# OBDII-Ist.net
KiCad netlist of a schematic drawn in Altium Designer
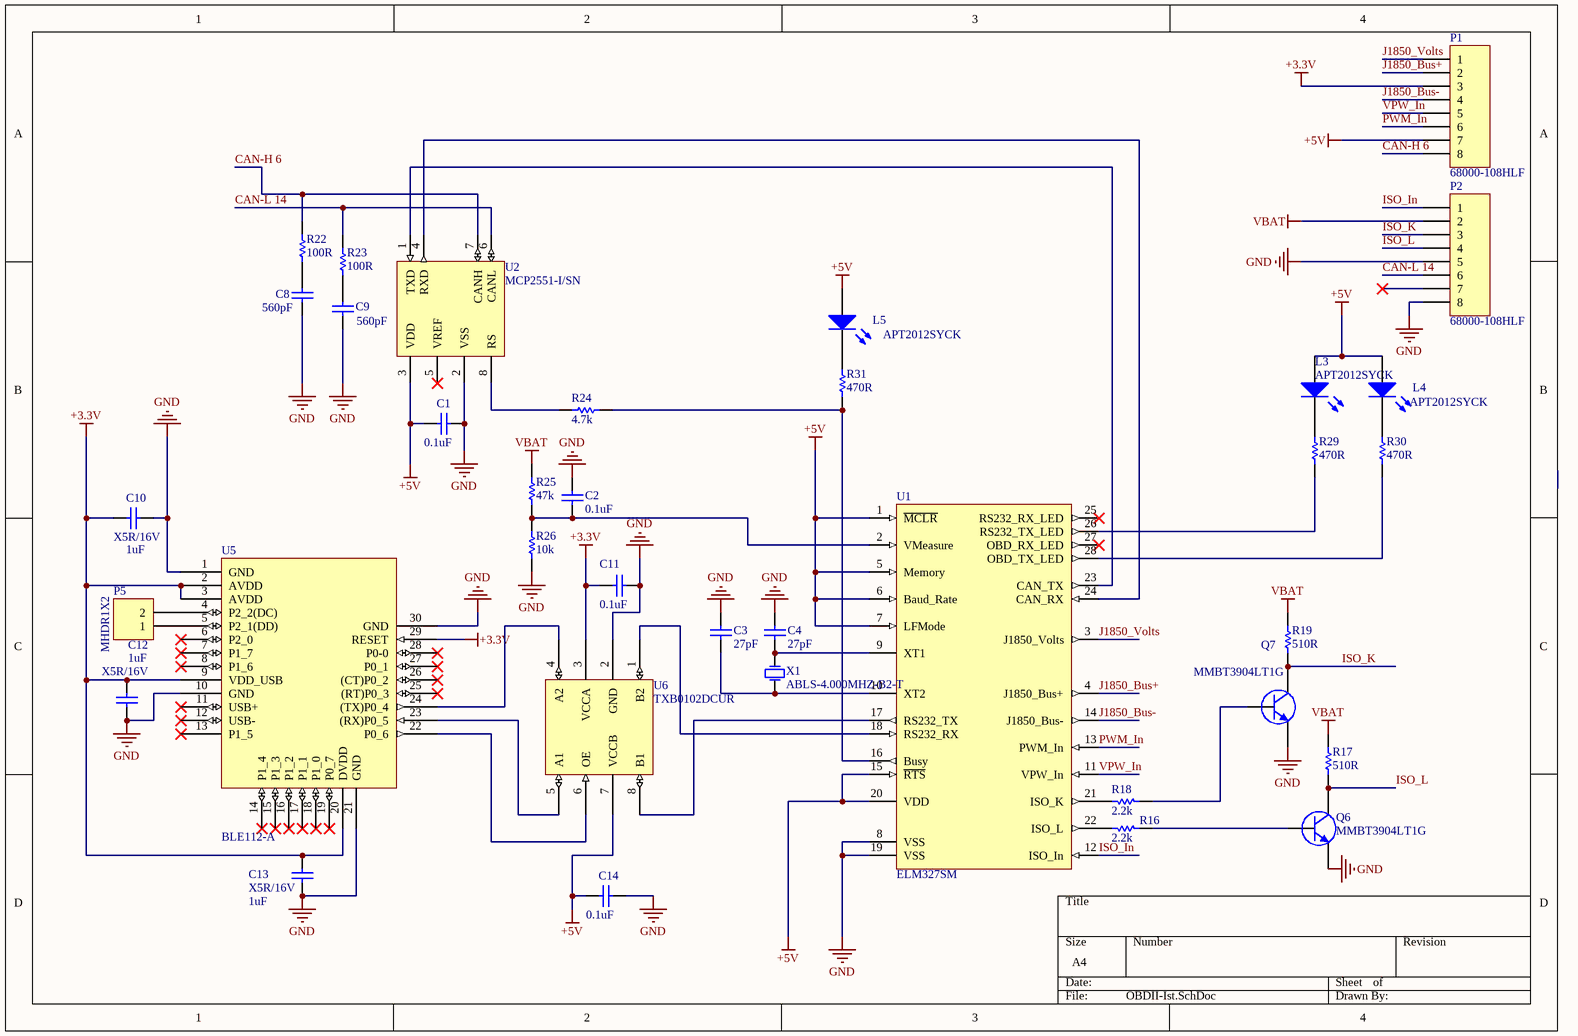
[diagram p0: OBDII-Ist.SchDoc]

(export (version "E")
  (design (tool "Eeschema 10.0.6"))
  (components
    (comp (ref "C1")
      (value "0.1uF")
      (footprint "1608[0603]")
      (description "Surface-Mount Ceramic Multilayer Capacitor, 0.1uF, X7R, 10% Tolerance, 0603 Size, 25V")
      (fields (field (name "PUBLISHER") "Altium Limited"))
      (libsource (lib "OBDII-components") (part "CGA3E2X7R1E104K080AA"))
    )
    (comp (ref "C2")
      (value "0.1uF")
      (footprint "1608[0603]")
      (description "Surface-Mount Ceramic Multilayer Capacitor, 0.1uF, X7R, 10% Tolerance, 0603 Size, 25V")
      (fields (field (name "PUBLISHER") "Altium Limited"))
      (libsource (lib "OBDII-components") (part "CGA3E2X7R1E104K080AA"))
    )
    (comp (ref "C3")
      (value "27pF")
      (footprint "1608[0603]")
      (description "Surface-Mount Ceramic Multilayer Capacitor, 27pF, 5% Tolerance, 0603 Size, 50V")
      (fields (field (name "PUBLISHER") "Altium Limited"))
      (libsource (lib "OBDII-components") (part "CC0603JRNPO9BN270"))
    )
    (comp (ref "C4")
      (value "27pF")
      (footprint "1608[0603]")
      (description "Surface-Mount Ceramic Multilayer Capacitor, 27pF, 5% Tolerance, 0603 Size, 50V")
      (fields (field (name "PUBLISHER") "Altium Limited"))
      (libsource (lib "OBDII-components") (part "CC0603JRNPO9BN270"))
    )
    (comp (ref "C8")
      (value "560pF")
      (footprint "0402")
      (description "Surface-Mount Ceramic Multilayer Capacitor, 560pF, 5% Tolerance, 0402 Size, 50V")
      (fields (field (name "PUBLISHER") "Altium Limited"))
      (libsource (lib "OBDII-components") (part "C0402C561J5GACTU"))
    )
    (comp (ref "C9")
      (value "560pF")
      (footprint "0402")
      (description "Surface-Mount Ceramic Multilayer Capacitor, 560pF, 5% Tolerance, 0402 Size, 50V")
      (fields (field (name "PUBLISHER") "Altium Limited"))
      (libsource (lib "OBDII-components") (part "C0402C561J5GACTU"))
    )
    (comp (ref "C10")
      (value "X5R/16V")
      (footprint "0402")
      (description "Capacitor (Semiconductor SIM Model)")
      (fields (field (name "ALTIUM_VALUE") "1uF") (field (name "PUBLISHER") "Altium Limited"))
      (libsource (lib "Miscellaneous Devices") (part "Cap Semi"))
    )
    (comp (ref "C11")
      (value "0.1uF")
      (footprint "1608[0603]")
      (description "Surface-Mount Ceramic Multilayer Capacitor, 0.1uF, X7R, 10% Tolerance, 0603 Size, 25V")
      (fields (field (name "PUBLISHER") "Altium Limited"))
      (libsource (lib "OBDII-components") (part "CGA3E2X7R1E104K080AA"))
    )
    (comp (ref "C12")
      (value "X5R/16V")
      (footprint "0402")
      (description "Capacitor (Semiconductor SIM Model)")
      (fields (field (name "ALTIUM_VALUE") "1uF") (field (name "PUBLISHER") "Altium Limited"))
      (libsource (lib "Miscellaneous Devices") (part "Cap Semi"))
    )
    (comp (ref "C13")
      (value "X5R/16V")
      (footprint "0402")
      (description "Capacitor (Semiconductor SIM Model)")
      (fields (field (name "ALTIUM_VALUE") "1uF") (field (name "PUBLISHER") "Altium Limited"))
      (libsource (lib "Miscellaneous Devices") (part "Cap Semi"))
    )
    (comp (ref "C14")
      (value "0.1uF")
      (footprint "1608[0603]")
      (description "Surface-Mount Ceramic Multilayer Capacitor, 0.1uF, X7R, 10% Tolerance, 0603 Size, 25V")
      (fields (field (name "PUBLISHER") "Altium Limited"))
      (libsource (lib "OBDII-components") (part "CGA3E2X7R1E104K080AA"))
    )
    (comp (ref "L3")
      (value "APT2012SYCK")
      (footprint "LED-0805")
      (description "Typical BLUE SiC LED")
      (libsource (lib "OBDII-components") (part "APT2012SYCK"))
    )
    (comp (ref "L4")
      (value "APT2012SYCK")
      (footprint "LED-0805")
      (description "Typical BLUE SiC LED")
      (libsource (lib "OBDII-components") (part "APT2012SYCK"))
    )
    (comp (ref "L5")
      (value "APT2012SYCK")
      (footprint "LED-0805")
      (description "Typical BLUE SiC LED")
      (libsource (lib "OBDII-components") (part "APT2012SYCK"))
    )
    (comp (ref "P1")
      (value "68000-108HLF")
      (footprint "HDR1X8")
      (description "Header, 8-Pin, 2.54 pitch, 1 row")
      (fields (field (name "PUBLISHER") "Altium Limited"))
      (libsource (lib "OBDII-components") (part "68000-108HLF"))
    )
    (comp (ref "P2")
      (value "68000-108HLF")
      (footprint "HDR1X8")
      (description "Header, 8-Pin, 2.54 pitch, 1 row")
      (fields (field (name "PUBLISHER") "Altium Limited"))
      (libsource (lib "OBDII-components") (part "68000-108HLF"))
    )
    (comp (ref "P5")
      (value "MHDR1X2")
      (footprint "MHDR1X2")
      (description "Header, 2-Pin")
      (fields (field (name "PUBLISHER") "Altium Limited"))
      (libsource (lib "OBDII-components") (part "MHDR1X2"))
    )
    (comp (ref "Q6")
      (value "MMBT3904LT1G")
      (footprint "SOT23")
      (description "NPN 3904 General Purpose Amplifier")
      (fields
        (field (name "MANUFACTURER") "ON Semiconductor")
        (field (name "PUBLISHER") "Vanteon")
        (field (name "APPROVED") "Yes by Implemenation")
      )
      (libsource (lib "OBDII-components") (part "MMBT3904L"))
    )
    (comp (ref "Q7")
      (value "MMBT3904LT1G")
      (footprint "SOT23")
      (description "NPN 3904 General Purpose Amplifier")
      (fields
        (field (name "MANUFACTURER") "ON Semiconductor")
        (field (name "PUBLISHER") "Vanteon")
        (field (name "APPROVED") "Yes by Implemenation")
      )
      (libsource (lib "OBDII-components") (part "MMBT3904L"))
    )
    (comp (ref "R16")
      (value "2.2k")
      (footprint "ERA-0805")
      (description "Rectangular Thick Film Chip Resistor, 2.2 kOhm, 0.1% Tolerance, 0805 Size, 0.125 W")
      (libsource (lib "OBDII-components") (part "ERA6AEB222V"))
    )
    (comp (ref "R17")
      (value "510R")
      (footprint "ERJ-1210")
      (description "Rectangular Thick Film Chip Resistor, 510 Ohm, 1% Tolerance, 1210 Size, 0.5 W")
      (libsource (lib "OBDII-components") (part "ERJ14NF5100U"))
    )
    (comp (ref "R18")
      (value "2.2k")
      (footprint "ERA-0805")
      (description "Rectangular Thick Film Chip Resistor, 2.2 kOhm, 0.1% Tolerance, 0805 Size, 0.125 W")
      (libsource (lib "OBDII-components") (part "ERA6AEB222V"))
    )
    (comp (ref "R19")
      (value "510R")
      (footprint "ERJ-1210")
      (description "Rectangular Thick Film Chip Resistor, 510 Ohm, 1% Tolerance, 1210 Size, 0.5 W")
      (libsource (lib "OBDII-components") (part "ERJ14NF5100U"))
    )
    (comp (ref "R22")
      (value "100R")
      (footprint "ERA-0805")
      (description "Rectangular Thick Film Chip Resistor, 100 Ohm, 0.1% Tolerance, 0805 Size, 0.125 W")
      (libsource (lib "OBDII-components") (part "ERA6AEB101V"))
    )
    (comp (ref "R23")
      (value "100R")
      (footprint "ERA-0805")
      (description "Rectangular Thick Film Chip Resistor, 100 Ohm, 0.1% Tolerance, 0805 Size, 0.125 W")
      (libsource (lib "OBDII-components") (part "ERA6AEB101V"))
    )
    (comp (ref "R24")
      (value "4.7k")
      (footprint "ERA-0805")
      (description "Rectangular Thick Film Chip Resistor, 4.7 kOhm, 0.1% Tolerance, 0805 Size, 0.125 W")
      (libsource (lib "OBDII-components") (part "ERA6AEB472V"))
    )
    (comp (ref "R25")
      (value "47k")
      (footprint "ERA-0805")
      (description "Rectangular Thick Film Chip Resistor, 47 kOhm, 0.1% Tolerance, 0805 Size, 0.125 W")
      (libsource (lib "OBDII-components") (part "ERA6AEB473V"))
    )
    (comp (ref "R26")
      (value "10k")
      (footprint "ERA-0805")
      (description "Rectangular Thick Film Chip Resistor, 10 kOhm, 0.1% Tolerance, 0805 Size, 0.125 W")
      (libsource (lib "OBDII-components") (part "ERA6AEB103V"))
    )
    (comp (ref "R29")
      (value "470R")
      (footprint "ERA-0805")
      (description "Rectangular Thick Film Chip Resistor, 470 Ohm, 0.1% Tolerance, 0805 Size, 0.125 W")
      (libsource (lib "OBDII-components") (part "ERA6AEB471V"))
    )
    (comp (ref "R30")
      (value "470R")
      (footprint "ERA-0805")
      (description "Rectangular Thick Film Chip Resistor, 470 Ohm, 0.1% Tolerance, 0805 Size, 0.125 W")
      (libsource (lib "OBDII-components") (part "ERA6AEB471V"))
    )
    (comp (ref "R31")
      (value "470R")
      (footprint "ERA-0805")
      (description "Rectangular Thick Film Chip Resistor, 470 Ohm, 0.1% Tolerance, 0805 Size, 0.125 W")
      (libsource (lib "OBDII-components") (part "ERA6AEB471V"))
    )
    (comp (ref "U1")
      (value "ELM327SM")
      (footprint "SOIC127P1030X264-28N")
      (description "OBDII Interpreter IC")
      (fields (field (name "MANUFACTURER") "Elm Electronics"))
      (libsource (lib "OBDII-components") (part "ELM327_SOIC"))
    )
    (comp (ref "U2")
      (value "MCP2551-I/SN")
      (footprint "SOIC8N")
      (description "IC TRANSCEIVER CAN HI-SPD 8-SOIC")
      (fields (field (name "MANUFACTURER") "Microchip Technology"))
      (libsource (lib "OBDII-components") (part "MCP2551-I/SN"))
    )
    (comp (ref "U5")
      (value "BLE112-A")
      (footprint "BLE112-A - II")
      (description "BLE112 Bluetooth Smart Module")
      (libsource (lib "OBDII-components") (part "BLE112-A"))
    )
    (comp (ref "U6")
      (value "TXB0102DCUR")
      (footprint "TXB0102DCUR")
      (description "2-Bit Bidirectional Voltage-Level Translator with Auto Direction Sensing and +/-15-kV ESD Protect")
      (libsource (lib "OBDII-components") (part "TXB0102DCUR"))
    )
    (comp (ref "X1")
      (value "ABLS-4.000MHZ-B2-T")
      (footprint "HC-49/US")
      (description "CRYSTAL 4.000 MHZ 18PF SMD")
      (fields (field (name "MANUFACTURER") "Abracon"))
      (libsource (lib "OBDII-components") (part "ABLS-4.000MHZ-B2-T"))
    )
  )
  (nets
    (net (code "1") (name "+3.3V") (class "Default")
      (node (ref "C10") (pin "1") (pinfunction "1_1") (pintype "passive"))
      (node (ref "C11") (pin "1") (pinfunction "1_1") (pintype "passive"))
      (node (ref "C12") (pin "2") (pinfunction "2_2") (pintype "passive"))
      (node (ref "C13") (pin "2") (pinfunction "2_2") (pintype "passive"))
      (node (ref "P1") (pin "3") (pinfunction "3_3") (pintype "passive"))
      (node (ref "U5") (pin "2") (pinfunction "AVDD_2") (pintype "power_in"))
      (node (ref "U5") (pin "20") (pinfunction "DVDD_20") (pintype "power_in"))
      (node (ref "U5") (pin "29") (pinfunction "RESET_29") (pintype "input"))
      (node (ref "U5") (pin "3") (pinfunction "AVDD_3") (pintype "power_in"))
      (node (ref "U5") (pin "9") (pinfunction "VDD_USB_9") (pintype "power_in"))
      (node (ref "U6") (pin "3") (pinfunction "VCCA_3") (pintype "power_in"))
    )
    (net (code "2") (name "+5V") (class "Default")
      (node (ref "C1") (pin "1") (pinfunction "1_1") (pintype "passive"))
      (node (ref "C14") (pin "1") (pinfunction "1_1") (pintype "passive"))
      (node (ref "L3") (pin "1") (pinfunction "A_1") (pintype "passive"))
      (node (ref "L4") (pin "1") (pinfunction "A_1") (pintype "passive"))
      (node (ref "L5") (pin "1") (pinfunction "A_1") (pintype "passive"))
      (node (ref "P1") (pin "7") (pinfunction "7_7") (pintype "passive"))
      (node (ref "U1") (pin "1") (pinfunction "~{MCLR}_1") (pintype "input"))
      (node (ref "U1") (pin "15") (pinfunction "~{RTS}_15") (pintype "input"))
      (node (ref "U1") (pin "20") (pinfunction "VDD_20") (pintype "power_in"))
      (node (ref "U1") (pin "5") (pinfunction "Memory_5") (pintype "input"))
      (node (ref "U1") (pin "6") (pinfunction "Baud_Rate_6") (pintype "input"))
      (node (ref "U1") (pin "7") (pinfunction "LFMode_7") (pintype "input"))
      (node (ref "U2") (pin "3") (pinfunction "VDD_3") (pintype "power_in"))
      (node (ref "U6") (pin "7") (pinfunction "VCCB_7") (pintype "power_in"))
    )
    (net (code "3") (name "/CAN-H 6") (class "Default")
      (node (ref "P1") (pin "8") (pinfunction "8_8") (pintype "passive"))
      (node (ref "R22") (pin "2") (pinfunction "2_2") (pintype "passive"))
      (node (ref "U2") (pin "7") (pinfunction "CANH_7") (pintype "bidirectional"))
    )
    (net (code "4") (name "/CAN-L 14") (class "Default")
      (node (ref "P2") (pin "6") (pinfunction "6_6") (pintype "passive"))
      (node (ref "R23") (pin "2") (pinfunction "2_2") (pintype "passive"))
      (node (ref "U2") (pin "6") (pinfunction "CANL_6") (pintype "bidirectional"))
    )
    (net (code "5") (name "/ISO_In") (class "Default")
      (node (ref "P2") (pin "1") (pinfunction "1_1") (pintype "passive"))
      (node (ref "U1") (pin "12") (pinfunction "ISO_In_12") (pintype "input"))
    )
    (net (code "6") (name "/ISO_K") (class "Default")
      (node (ref "P2") (pin "3") (pinfunction "3_3") (pintype "passive"))
      (node (ref "Q7") (pin "3") (pinfunction "C_3") (pintype "passive"))
      (node (ref "R19") (pin "1") (pinfunction "1_1") (pintype "passive"))
    )
    (net (code "7") (name "/ISO_L") (class "Default")
      (node (ref "P2") (pin "4") (pinfunction "4_4") (pintype "passive"))
      (node (ref "Q6") (pin "3") (pinfunction "C_3") (pintype "passive"))
      (node (ref "R17") (pin "1") (pinfunction "1_1") (pintype "passive"))
    )
    (net (code "8") (name "/J1850_Bus+") (class "Default")
      (node (ref "P1") (pin "2") (pinfunction "2_2") (pintype "passive"))
      (node (ref "U1") (pin "4") (pinfunction "J1850_Bus+_4") (pintype "output"))
    )
    (net (code "9") (name "/J1850_Bus-") (class "Default")
      (node (ref "P1") (pin "4") (pinfunction "4_4") (pintype "passive"))
      (node (ref "U1") (pin "14") (pinfunction "J1850_Bus-_14") (pintype "output"))
    )
    (net (code "10") (name "/J1850_Volts") (class "Default")
      (node (ref "P1") (pin "1") (pinfunction "1_1") (pintype "passive"))
      (node (ref "U1") (pin "3") (pinfunction "J1850_Volts_3") (pintype "output"))
    )
    (net (code "11") (name "/PWM_In") (class "Default")
      (node (ref "P1") (pin "6") (pinfunction "6_6") (pintype "passive"))
      (node (ref "U1") (pin "13") (pinfunction "PWM_In_13") (pintype "input"))
    )
    (net (code "12") (name "/VPW_In") (class "Default")
      (node (ref "P1") (pin "5") (pinfunction "5_5") (pintype "passive"))
      (node (ref "U1") (pin "11") (pinfunction "VPW_In_11") (pintype "input"))
    )
    (net (code "13") (name "GND") (class "Default")
      (node (ref "C1") (pin "2") (pinfunction "2_2") (pintype "passive"))
      (node (ref "C10") (pin "2") (pinfunction "2_2") (pintype "passive"))
      (node (ref "C11") (pin "2") (pinfunction "2_2") (pintype "passive"))
      (node (ref "C12") (pin "1") (pinfunction "1_1") (pintype "passive"))
      (node (ref "C13") (pin "1") (pinfunction "1_1") (pintype "passive"))
      (node (ref "C14") (pin "2") (pinfunction "2_2") (pintype "passive"))
      (node (ref "C2") (pin "2") (pinfunction "2_2") (pintype "passive"))
      (node (ref "C3") (pin "2") (pinfunction "2_2") (pintype "passive"))
      (node (ref "C4") (pin "2") (pinfunction "2_2") (pintype "passive"))
      (node (ref "C8") (pin "1") (pinfunction "1_1") (pintype "passive"))
      (node (ref "C9") (pin "1") (pinfunction "1_1") (pintype "passive"))
      (node (ref "P2") (pin "5") (pinfunction "5_5") (pintype "passive"))
      (node (ref "P2") (pin "8") (pinfunction "8_8") (pintype "passive"))
      (node (ref "Q6") (pin "2") (pinfunction "E_2") (pintype "passive"))
      (node (ref "Q7") (pin "2") (pinfunction "E_2") (pintype "passive"))
      (node (ref "R26") (pin "1") (pinfunction "1_1") (pintype "passive"))
      (node (ref "U1") (pin "19") (pinfunction "VSS_19") (pintype "power_in"))
      (node (ref "U1") (pin "8") (pinfunction "VSS_8") (pintype "power_in"))
      (node (ref "U2") (pin "2") (pinfunction "VSS_2") (pintype "power_in"))
      (node (ref "U5") (pin "1") (pinfunction "GND_1") (pintype "power_in"))
      (node (ref "U5") (pin "10") (pinfunction "GND_10") (pintype "passive"))
      (node (ref "U5") (pin "21") (pinfunction "GND_21") (pintype "power_in"))
      (node (ref "U5") (pin "30") (pinfunction "GND_30") (pintype "power_in"))
      (node (ref "U6") (pin "2") (pinfunction "GND_2") (pintype "power_in"))
    )
    (net (code "14") (name "Net-(C8-Pad2)") (class "Default")
      (node (ref "C8") (pin "2") (pinfunction "2_2") (pintype "passive"))
      (node (ref "R22") (pin "1") (pinfunction "1_1") (pintype "passive"))
    )
    (net (code "15") (name "Net-(C9-Pad2)") (class "Default")
      (node (ref "C9") (pin "2") (pinfunction "2_2") (pintype "passive"))
      (node (ref "R23") (pin "1") (pinfunction "1_1") (pintype "passive"))
    )
    (net (code "16") (name "Net-(L3-K)") (class "Default")
      (node (ref "L3") (pin "2") (pinfunction "K_2") (pintype "passive"))
      (node (ref "R29") (pin "2") (pinfunction "2_2") (pintype "passive"))
    )
    (net (code "17") (name "Net-(L4-K)") (class "Default")
      (node (ref "L4") (pin "2") (pinfunction "K_2") (pintype "passive"))
      (node (ref "R30") (pin "2") (pinfunction "2_2") (pintype "passive"))
    )
    (net (code "18") (name "Net-(L5-K)") (class "Default")
      (node (ref "L5") (pin "2") (pinfunction "K_2") (pintype "passive"))
      (node (ref "R31") (pin "2") (pinfunction "2_2") (pintype "passive"))
    )
    (net (code "19") (name "Net-(Q6-B)") (class "Default")
      (node (ref "Q6") (pin "1") (pinfunction "B_1") (pintype "passive"))
      (node (ref "R16") (pin "1") (pinfunction "1_1") (pintype "passive"))
    )
    (net (code "20") (name "Net-(Q7-B)") (class "Default")
      (node (ref "Q7") (pin "1") (pinfunction "B_1") (pintype "passive"))
      (node (ref "R18") (pin "1") (pinfunction "1_1") (pintype "passive"))
    )
    (net (code "21") (name "Net-(U1-Busy)") (class "Default")
      (node (ref "R24") (pin "2") (pinfunction "2_2") (pintype "passive"))
      (node (ref "R31") (pin "1") (pinfunction "1_1") (pintype "passive"))
      (node (ref "U1") (pin "16") (pinfunction "Busy_16") (pintype "output"))
    )
    (net (code "22") (name "Net-(U1-CAN_RX)") (class "Default")
      (node (ref "U1") (pin "24") (pinfunction "CAN_RX_24") (pintype "input"))
      (node (ref "U2") (pin "4") (pinfunction "RXD_4") (pintype "output"))
    )
    (net (code "23") (name "Net-(U1-CAN_TX)") (class "Default")
      (node (ref "U1") (pin "23") (pinfunction "CAN_TX_23") (pintype "output"))
      (node (ref "U2") (pin "1") (pinfunction "TXD_1") (pintype "input"))
    )
    (net (code "24") (name "Net-(U1-ISO_K)") (class "Default")
      (node (ref "R18") (pin "2") (pinfunction "2_2") (pintype "passive"))
      (node (ref "U1") (pin "21") (pinfunction "ISO_K_21") (pintype "output"))
    )
    (net (code "25") (name "Net-(U1-ISO_L)") (class "Default")
      (node (ref "R16") (pin "2") (pinfunction "2_2") (pintype "passive"))
      (node (ref "U1") (pin "22") (pinfunction "ISO_L_22") (pintype "output"))
    )
    (net (code "26") (name "Net-(U1-OBD_TX_LED)") (class "Default")
      (node (ref "R30") (pin "1") (pinfunction "1_1") (pintype "passive"))
      (node (ref "U1") (pin "28") (pinfunction "OBD_TX_LED_28") (pintype "output"))
    )
    (net (code "27") (name "Net-(U1-RS232_RX)") (class "Default")
      (node (ref "U1") (pin "18") (pinfunction "RS232_RX_18") (pintype "input"))
      (node (ref "U6") (pin "1") (pinfunction "B2_1") (pintype "bidirectional"))
    )
    (net (code "28") (name "Net-(U1-RS232_TX)") (class "Default")
      (node (ref "U1") (pin "17") (pinfunction "RS232_TX_17") (pintype "output"))
      (node (ref "U6") (pin "8") (pinfunction "B1_8") (pintype "bidirectional"))
    )
    (net (code "29") (name "Net-(U1-RS232_TX_LED)") (class "Default")
      (node (ref "R29") (pin "1") (pinfunction "1_1") (pintype "passive"))
      (node (ref "U1") (pin "26") (pinfunction "RS232_TX_LED_26") (pintype "output"))
    )
    (net (code "30") (name "Net-(U1-VMeasure)") (class "Default")
      (node (ref "C2") (pin "1") (pinfunction "1_1") (pintype "passive"))
      (node (ref "R25") (pin "1") (pinfunction "1_1") (pintype "passive"))
      (node (ref "R26") (pin "2") (pinfunction "2_2") (pintype "passive"))
      (node (ref "U1") (pin "2") (pinfunction "VMeasure_2") (pintype "input"))
    )
    (net (code "31") (name "Net-(U1-XT1)") (class "Default")
      (node (ref "C4") (pin "1") (pinfunction "1_1") (pintype "passive"))
      (node (ref "U1") (pin "9") (pinfunction "XT1_9") (pintype "passive"))
      (node (ref "X1") (pin "2") (pinfunction "OSC2_2") (pintype "passive"))
    )
    (net (code "32") (name "Net-(U1-XT2)") (class "Default")
      (node (ref "C3") (pin "1") (pinfunction "1_1") (pintype "passive"))
      (node (ref "U1") (pin "10") (pinfunction "XT2_10") (pintype "passive"))
      (node (ref "X1") (pin "1") (pinfunction "OSC1_1") (pintype "passive"))
    )
    (net (code "33") (name "Net-(U2-RS)") (class "Default")
      (node (ref "R24") (pin "1") (pinfunction "1_1") (pintype "passive"))
      (node (ref "U2") (pin "8") (pinfunction "RS_8") (pintype "passive"))
    )
    (net (code "34") (name "Net-(U5-(RX)P0_5)") (class "Default")
      (node (ref "U5") (pin "23") (pinfunction "(RX)P0_5_23") (pintype "input"))
      (node (ref "U6") (pin "5") (pinfunction "A1_5") (pintype "bidirectional"))
    )
    (net (code "35") (name "Net-(U5-(TX)P0_4)") (class "Default")
      (node (ref "U5") (pin "24") (pinfunction "(TX)P0_4_24") (pintype "output"))
      (node (ref "U6") (pin "4") (pinfunction "A2_4") (pintype "bidirectional"))
    )
    (net (code "36") (name "Net-(U5-P0_6)") (class "Default")
      (node (ref "U5") (pin "22") (pinfunction "P0_6_22") (pintype "output"))
      (node (ref "U6") (pin "6") (pinfunction "OE_6") (pintype "input"))
    )
    (net (code "37") (name "Net-(U5-P2_1(DD))") (class "Default")
      (node (ref "P5") (pin "1") (pinfunction "1_1") (pintype "passive"))
      (node (ref "U5") (pin "5") (pinfunction "P2_1(DD)_5") (pintype "bidirectional"))
    )
    (net (code "38") (name "Net-(U5-P2_2(DC))") (class "Default")
      (node (ref "P5") (pin "2") (pinfunction "2_2") (pintype "passive"))
      (node (ref "U5") (pin "4") (pinfunction "P2_2(DC)_4") (pintype "bidirectional"))
    )
    (net (code "39") (name "VBAT") (class "Default")
      (node (ref "P2") (pin "2") (pinfunction "2_2") (pintype "passive"))
      (node (ref "R17") (pin "2") (pinfunction "2_2") (pintype "passive"))
      (node (ref "R19") (pin "2") (pinfunction "2_2") (pintype "passive"))
      (node (ref "R25") (pin "2") (pinfunction "2_2") (pintype "passive"))
    )
    (net (code "40") (name "unconnected-(P2-Pad7)") (class "Default")
      (node (ref "P2") (pin "7") (pinfunction "7_7") (pintype "passive+no_connect"))
    )
    (net (code "41") (name "unconnected-(U1-OBD_RX_LED-Pad27)") (class "Default")
      (node (ref "U1") (pin "27") (pinfunction "OBD_RX_LED_27") (pintype "output+no_connect"))
    )
    (net (code "42") (name "unconnected-(U1-RS232_RX_LED-Pad25)") (class "Default")
      (node (ref "U1") (pin "25") (pinfunction "RS232_RX_LED_25") (pintype "output+no_connect"))
    )
    (net (code "43") (name "unconnected-(U2-VREF-Pad5)") (class "Default")
      (node (ref "U2") (pin "5") (pinfunction "VREF_5") (pintype "passive+no_connect"))
    )
    (net (code "44") (name "unconnected-(U5-(CT)P0_2-Pad26)") (class "Default")
      (node (ref "U5") (pin "26") (pinfunction "(CT)P0_2_26") (pintype "bidirectional+no_connect"))
    )
    (net (code "45") (name "unconnected-(U5-(RT)P0_3-Pad25)") (class "Default")
      (node (ref "U5") (pin "25") (pinfunction "(RT)P0_3_25") (pintype "bidirectional+no_connect"))
    )
    (net (code "46") (name "unconnected-(U5-P0-0-Pad28)") (class "Default")
      (node (ref "U5") (pin "28") (pinfunction "P0-0_28") (pintype "bidirectional+no_connect"))
    )
    (net (code "47") (name "unconnected-(U5-P0_1-Pad27)") (class "Default")
      (node (ref "U5") (pin "27") (pinfunction "P0_1_27") (pintype "bidirectional+no_connect"))
    )
    (net (code "48") (name "unconnected-(U5-P0_7-Pad19)") (class "Default")
      (node (ref "U5") (pin "19") (pinfunction "P0_7_19") (pintype "bidirectional+no_connect"))
    )
    (net (code "49") (name "unconnected-(U5-P1_0-Pad18)") (class "Default")
      (node (ref "U5") (pin "18") (pinfunction "P1_0_18") (pintype "bidirectional+no_connect"))
    )
    (net (code "50") (name "unconnected-(U5-P1_1-Pad17)") (class "Default")
      (node (ref "U5") (pin "17") (pinfunction "P1_1_17") (pintype "bidirectional+no_connect"))
    )
    (net (code "51") (name "unconnected-(U5-P1_2-Pad16)") (class "Default")
      (node (ref "U5") (pin "16") (pinfunction "P1_2_16") (pintype "bidirectional+no_connect"))
    )
    (net (code "52") (name "unconnected-(U5-P1_3-Pad15)") (class "Default")
      (node (ref "U5") (pin "15") (pinfunction "P1_3_15") (pintype "bidirectional+no_connect"))
    )
    (net (code "53") (name "unconnected-(U5-P1_4-Pad14)") (class "Default")
      (node (ref "U5") (pin "14") (pinfunction "P1_4_14") (pintype "bidirectional+no_connect"))
    )
    (net (code "54") (name "unconnected-(U5-P1_5-Pad13)") (class "Default")
      (node (ref "U5") (pin "13") (pinfunction "P1_5_13") (pintype "passive+no_connect"))
    )
    (net (code "55") (name "unconnected-(U5-P1_6-Pad8)") (class "Default")
      (node (ref "U5") (pin "8") (pinfunction "P1_6_8") (pintype "bidirectional+no_connect"))
    )
    (net (code "56") (name "unconnected-(U5-P1_7-Pad7)") (class "Default")
      (node (ref "U5") (pin "7") (pinfunction "P1_7_7") (pintype "bidirectional+no_connect"))
    )
    (net (code "57") (name "unconnected-(U5-P2_0-Pad6)") (class "Default")
      (node (ref "U5") (pin "6") (pinfunction "P2_0_6") (pintype "bidirectional+no_connect"))
    )
    (net (code "58") (name "unconnected-(U5-USB+-Pad11)") (class "Default")
      (node (ref "U5") (pin "11") (pinfunction "USB+_11") (pintype "bidirectional+no_connect"))
    )
    (net (code "59") (name "unconnected-(U5-USB--Pad12)") (class "Default")
      (node (ref "U5") (pin "12") (pinfunction "USB-_12") (pintype "bidirectional+no_connect"))
    )
  )
)
